# RS485_RS232_Sheet.net
KiCad netlist of a schematic drawn in Altium Designer
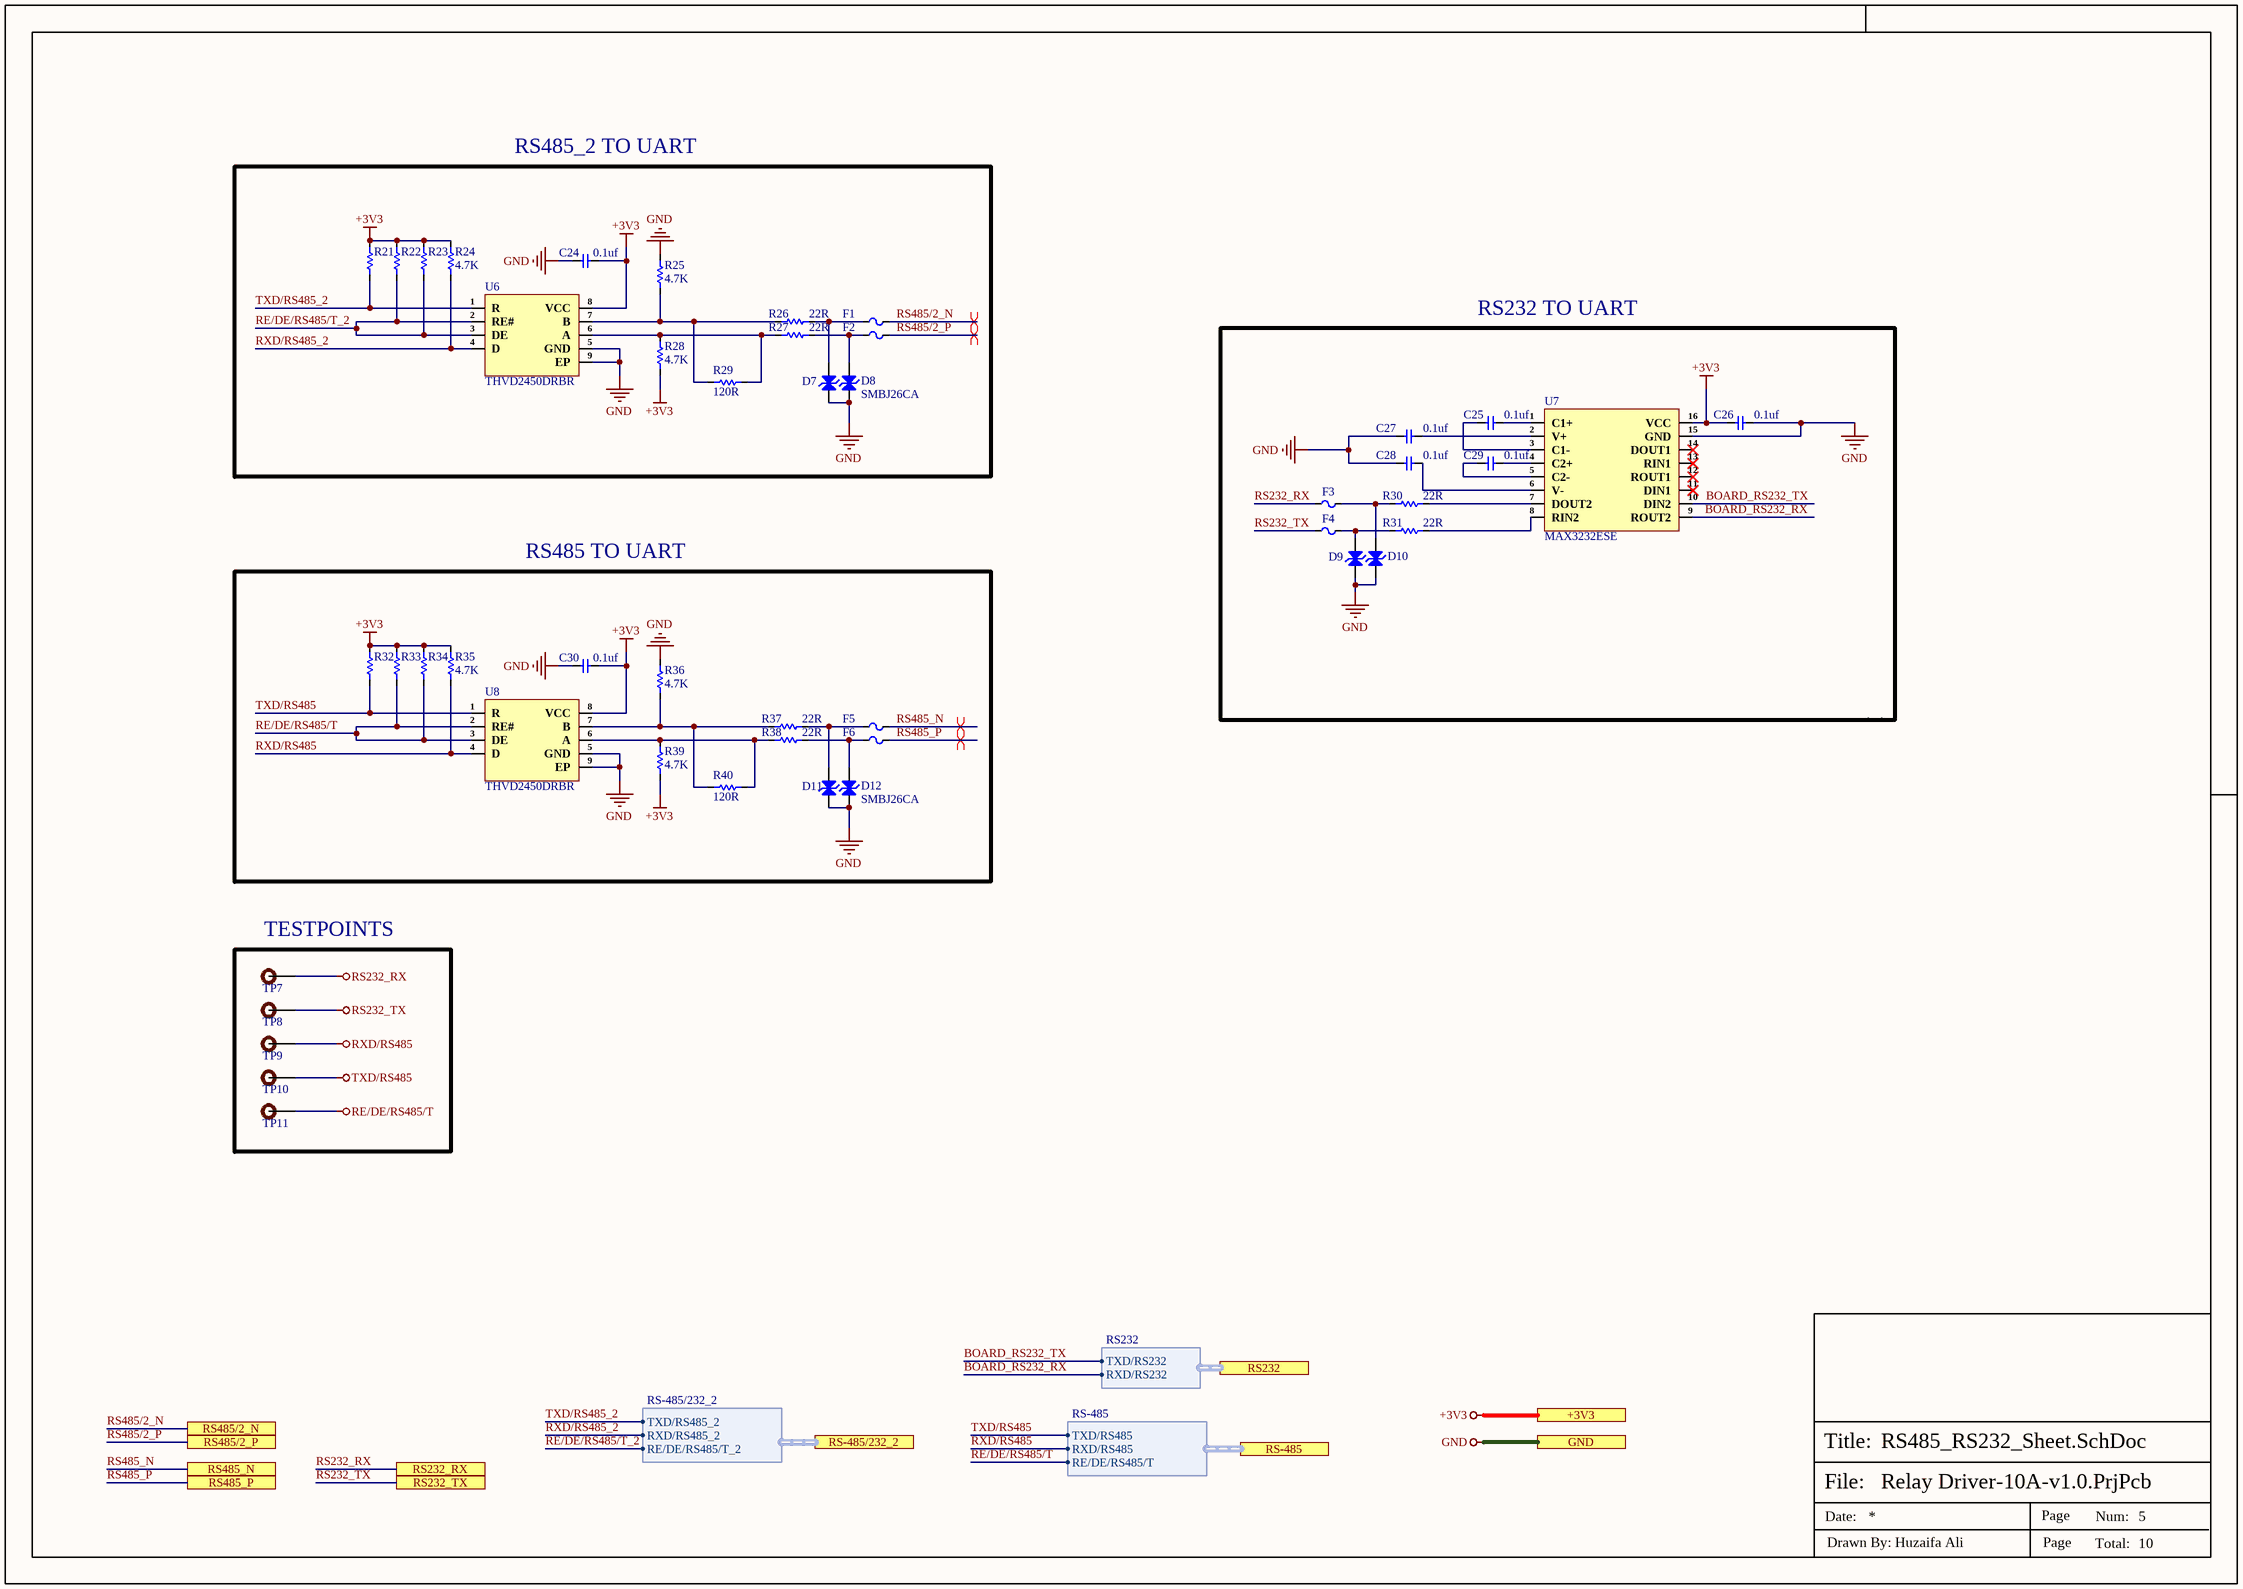
[diagram p0: RS485_RS232_Sheet.SchDoc]

(export (version "E")
  (design (tool "Eeschema 10.0.6"))
  (components
    (comp (ref "C24")
      (value "0.1uf")
      (footprint "Cap-0402")
      (description "CAP CER 0.1UF 100V X5R 0402")
      (fields
        (field (name "MANUFACTURER") "Murata")
        (field (name "MANUFACTURER PART NUMBER") "GRM155R62A104KE14D")
      )
      (libsource (lib "eSpark Libraries") (part "GRM155R62A104KE14D"))
    )
    (comp (ref "C25")
      (value "0.1uf")
      (footprint "Cap-0402")
      (description "CAP CER 0.1UF 100V X5R 0402")
      (fields
        (field (name "MANUFACTURER") "Murata")
        (field (name "MANUFACTURER PART NUMBER") "GRM155R62A104KE14D")
      )
      (libsource (lib "eSpark Libraries") (part "GRM155R62A104KE14D"))
    )
    (comp (ref "C26")
      (value "0.1uf")
      (footprint "Cap-0402")
      (description "CAP CER 0.1UF 100V X5R 0402")
      (fields
        (field (name "MANUFACTURER") "Murata")
        (field (name "MANUFACTURER PART NUMBER") "GRM155R62A104KE14D")
      )
      (libsource (lib "eSpark Libraries") (part "GRM155R62A104KE14D"))
    )
    (comp (ref "C27")
      (value "0.1uf")
      (footprint "Cap-0402")
      (description "CAP CER 0.1UF 100V X5R 0402")
      (fields
        (field (name "MANUFACTURER") "Murata")
        (field (name "MANUFACTURER PART NUMBER") "GRM155R62A104KE14D")
      )
      (libsource (lib "eSpark Libraries") (part "GRM155R62A104KE14D"))
    )
    (comp (ref "C28")
      (value "0.1uf")
      (footprint "Cap-0402")
      (description "CAP CER 0.1UF 100V X5R 0402")
      (fields
        (field (name "MANUFACTURER") "Murata")
        (field (name "MANUFACTURER PART NUMBER") "GRM155R62A104KE14D")
      )
      (libsource (lib "eSpark Libraries") (part "GRM155R62A104KE14D"))
    )
    (comp (ref "C29")
      (value "0.1uf")
      (footprint "Cap-0402")
      (description "CAP CER 0.1UF 100V X5R 0402")
      (fields
        (field (name "MANUFACTURER") "Murata")
        (field (name "MANUFACTURER PART NUMBER") "GRM155R62A104KE14D")
      )
      (libsource (lib "eSpark Libraries") (part "GRM155R62A104KE14D"))
    )
    (comp (ref "C30")
      (value "0.1uf")
      (footprint "Cap-0402")
      (description "CAP CER 0.1UF 100V X5R 0402")
      (fields
        (field (name "MANUFACTURER") "Murata")
        (field (name "MANUFACTURER PART NUMBER") "GRM155R62A104KE14D")
      )
      (libsource (lib "eSpark Libraries") (part "GRM155R62A104KE14D"))
    )
    (comp (ref "D7")
      (value "SMBJ26CA")
      (footprint "SMB Bi Directional")
      (description "SMB(DO-214AA) TVS ROHS")
      (fields (field (name "MANUFACTURER") "MSKSEMI") (field (name "LCSC PART NUMBER") "C5331111"))
      (libsource (lib "eSpark Libraries") (part "SMBJ26CA"))
    )
    (comp (ref "D8")
      (value "SMBJ26CA")
      (footprint "SMB Bi Directional")
      (description "SMB(DO-214AA) TVS ROHS")
      (fields (field (name "MANUFACTURER") "MSKSEMI") (field (name "LCSC PART NUMBER") "C5331111"))
      (libsource (lib "eSpark Libraries") (part "SMBJ26CA"))
    )
    (comp (ref "D9")
      (value "SMBJ26CA")
      (footprint "SMB Bi Directional")
      (description "SMB(DO-214AA) TVS ROHS")
      (fields (field (name "MANUFACTURER") "MSKSEMI") (field (name "LCSC PART NUMBER") "C5331111"))
      (libsource (lib "eSpark Libraries") (part "SMBJ26CA"))
    )
    (comp (ref "D10")
      (value "SMBJ26CA")
      (footprint "SMB Bi Directional")
      (description "SMB(DO-214AA) TVS ROHS")
      (fields (field (name "MANUFACTURER") "MSKSEMI") (field (name "LCSC PART NUMBER") "C5331111"))
      (libsource (lib "eSpark Libraries") (part "SMBJ26CA"))
    )
    (comp (ref "D11")
      (value "SMBJ26CA")
      (footprint "SMB Bi Directional")
      (description "SMB(DO-214AA) TVS ROHS")
      (fields (field (name "MANUFACTURER") "MSKSEMI") (field (name "LCSC PART NUMBER") "C5331111"))
      (libsource (lib "eSpark Libraries") (part "SMBJ26CA"))
    )
    (comp (ref "D12")
      (value "SMBJ26CA")
      (footprint "SMB Bi Directional")
      (description "SMB(DO-214AA) TVS ROHS")
      (fields (field (name "MANUFACTURER") "MSKSEMI") (field (name "LCSC PART NUMBER") "C5331111"))
      (libsource (lib "eSpark Libraries") (part "SMBJ26CA"))
    )
    (comp (ref "F1")
      (value "SMD0805P020TF")
      (footprint "Fuse-0805")
      (description "9V 200mA 100A 500mA 0805 Resettable Fuses ROHS")
      (fields (field (name "MANUFACTURER") "RUILON") (field (name "LCSC PART NUMBER") "C20976"))
      (libsource (lib "eSpark_centralized_Library(2022)") (part "SMD0805P020TF"))
    )
    (comp (ref "F2")
      (value "SMD0805P020TF")
      (footprint "Fuse-0805")
      (description "9V 200mA 100A 500mA 0805 Resettable Fuses ROHS")
      (fields (field (name "MANUFACTURER") "RUILON") (field (name "LCSC PART NUMBER") "C20976"))
      (libsource (lib "eSpark_centralized_Library(2022)") (part "SMD0805P020TF"))
    )
    (comp (ref "F3")
      (value "SMD0805P020TF")
      (footprint "Fuse-0805")
      (description "9V 200mA 100A 500mA 0805 Resettable Fuses ROHS")
      (fields (field (name "MANUFACTURER") "RUILON") (field (name "LCSC PART NUMBER") "C20976"))
      (libsource (lib "eSpark Libraries") (part "SMD0805P020TF"))
    )
    (comp (ref "F4")
      (value "SMD0805P020TF")
      (footprint "Fuse-0805")
      (description "9V 200mA 100A 500mA 0805 Resettable Fuses ROHS")
      (fields (field (name "MANUFACTURER") "RUILON") (field (name "LCSC PART NUMBER") "C20976"))
      (libsource (lib "eSpark Libraries") (part "SMD0805P020TF"))
    )
    (comp (ref "F5")
      (value "SMD0805P020TF")
      (footprint "Fuse-0805")
      (description "9V 200mA 100A 500mA 0805 Resettable Fuses ROHS")
      (fields (field (name "MANUFACTURER") "RUILON") (field (name "LCSC PART NUMBER") "C20976"))
      (libsource (lib "eSpark_centralized_Library(2022)") (part "SMD0805P020TF"))
    )
    (comp (ref "F6")
      (value "SMD0805P020TF")
      (footprint "Fuse-0805")
      (description "9V 200mA 100A 500mA 0805 Resettable Fuses ROHS")
      (fields (field (name "MANUFACTURER") "RUILON") (field (name "LCSC PART NUMBER") "C20976"))
      (libsource (lib "eSpark_centralized_Library(2022)") (part "SMD0805P020TF"))
    )
    (comp (ref "R21")
      (value "4.7K")
      (footprint "Res-0402")
      (description "RES 4.7K OHM 1% 1/16W 0402")
      (fields
        (field (name "MANUFACTURER") "Yageo")
        (field (name "MANUFACTURER PART NUMBER") "RC0402FR-074K7L")
      )
      (libsource (lib "eSpark Libraries") (part "RC0402FR-074K7L"))
    )
    (comp (ref "R22")
      (value "4.7K")
      (footprint "Res-0402")
      (description "RES 4.7K OHM 1% 1/16W 0402")
      (fields
        (field (name "MANUFACTURER") "Yageo")
        (field (name "MANUFACTURER PART NUMBER") "RC0402FR-074K7L")
      )
      (libsource (lib "eSpark Libraries") (part "RC0402FR-074K7L"))
    )
    (comp (ref "R23")
      (value "4.7K")
      (footprint "Res-0402")
      (description "RES 4.7K OHM 1% 1/16W 0402")
      (fields
        (field (name "MANUFACTURER") "Yageo")
        (field (name "MANUFACTURER PART NUMBER") "RC0402FR-074K7L")
      )
      (libsource (lib "eSpark Libraries") (part "RC0402FR-074K7L"))
    )
    (comp (ref "R24")
      (value "4.7K")
      (footprint "Res-0402")
      (description "RES 4.7K OHM 1% 1/16W 0402")
      (fields
        (field (name "MANUFACTURER") "Yageo")
        (field (name "MANUFACTURER PART NUMBER") "RC0402FR-074K7L")
      )
      (libsource (lib "eSpark Libraries") (part "RC0402FR-074K7L"))
    )
    (comp (ref "R25")
      (value "4.7K")
      (footprint "Res-0402")
      (description "RES 4.7K OHM 1% 1/16W 0402")
      (fields
        (field (name "MANUFACTURER") "Yageo")
        (field (name "MANUFACTURER PART NUMBER") "RC0402FR-074K7L")
      )
      (libsource (lib "eSpark Libraries") (part "RC0402FR-074K7L"))
    )
    (comp (ref "R26")
      (value "22R")
      (footprint "Res-0201")
      (description "RES 22 OHM 1% 1/20W 0201")
      (fields
        (field (name "MANUFACTURER") "Yageo")
        (field (name "MANUFACTURER PART NUMBER") "RC0201FR-0722RL")
      )
      (libsource (lib "eSpark Libraries") (part "RC0201FR-0722RL"))
    )
    (comp (ref "R27")
      (value "22R")
      (footprint "Res-0201")
      (description "RES 22 OHM 1% 1/20W 0201")
      (fields
        (field (name "MANUFACTURER") "Yageo")
        (field (name "MANUFACTURER PART NUMBER") "RC0201FR-0722RL")
      )
      (libsource (lib "eSpark Libraries") (part "RC0201FR-0722RL"))
    )
    (comp (ref "R28")
      (value "4.7K")
      (footprint "Res-0402")
      (description "RES 4.7K OHM 1% 1/16W 0402")
      (fields
        (field (name "MANUFACTURER") "Yageo")
        (field (name "MANUFACTURER PART NUMBER") "RC0402FR-074K7L")
      )
      (libsource (lib "eSpark Libraries") (part "RC0402FR-074K7L"))
    )
    (comp (ref "R29")
      (value "120R")
      (footprint "Res-0603")
      (description "RES 120 OHM 5% 1/10W 0603")
      (fields
        (field (name "MANUFACTURER") "Yageo")
        (field (name "MANUFACTURER PART NUMBER") "RC0603JR-07120RL")
      )
      (libsource (lib "eSpark Libraries") (part "RC0603JR-07120RL"))
    )
    (comp (ref "R30")
      (value "22R")
      (footprint "Res-0201")
      (description "RES 22 OHM 1% 1/20W 0201")
      (fields
        (field (name "MANUFACTURER") "Yageo")
        (field (name "MANUFACTURER PART NUMBER") "RC0201FR-0722RL")
      )
      (libsource (lib "eSpark Libraries") (part "RC0201FR-0722RL"))
    )
    (comp (ref "R31")
      (value "22R")
      (footprint "Res-0201")
      (description "RES 22 OHM 1% 1/20W 0201")
      (fields
        (field (name "MANUFACTURER") "Yageo")
        (field (name "MANUFACTURER PART NUMBER") "RC0201FR-0722RL")
      )
      (libsource (lib "eSpark Libraries") (part "RC0201FR-0722RL"))
    )
    (comp (ref "R32")
      (value "4.7K")
      (footprint "Res-0402")
      (description "RES 4.7K OHM 1% 1/16W 0402")
      (fields
        (field (name "MANUFACTURER") "Yageo")
        (field (name "MANUFACTURER PART NUMBER") "RC0402FR-074K7L")
      )
      (libsource (lib "eSpark Libraries") (part "RC0402FR-074K7L"))
    )
    (comp (ref "R33")
      (value "4.7K")
      (footprint "Res-0402")
      (description "RES 4.7K OHM 1% 1/16W 0402")
      (fields
        (field (name "MANUFACTURER") "Yageo")
        (field (name "MANUFACTURER PART NUMBER") "RC0402FR-074K7L")
      )
      (libsource (lib "eSpark Libraries") (part "RC0402FR-074K7L"))
    )
    (comp (ref "R34")
      (value "4.7K")
      (footprint "Res-0402")
      (description "RES 4.7K OHM 1% 1/16W 0402")
      (fields
        (field (name "MANUFACTURER") "Yageo")
        (field (name "MANUFACTURER PART NUMBER") "RC0402FR-074K7L")
      )
      (libsource (lib "eSpark Libraries") (part "RC0402FR-074K7L"))
    )
    (comp (ref "R35")
      (value "4.7K")
      (footprint "Res-0402")
      (description "RES 4.7K OHM 1% 1/16W 0402")
      (fields
        (field (name "MANUFACTURER") "Yageo")
        (field (name "MANUFACTURER PART NUMBER") "RC0402FR-074K7L")
      )
      (libsource (lib "eSpark Libraries") (part "RC0402FR-074K7L"))
    )
    (comp (ref "R36")
      (value "4.7K")
      (footprint "Res-0402")
      (description "RES 4.7K OHM 1% 1/16W 0402")
      (fields
        (field (name "MANUFACTURER") "Yageo")
        (field (name "MANUFACTURER PART NUMBER") "RC0402FR-074K7L")
      )
      (libsource (lib "eSpark Libraries") (part "RC0402FR-074K7L"))
    )
    (comp (ref "R37")
      (value "22R")
      (footprint "Res-0201")
      (description "RES 22 OHM 1% 1/20W 0201")
      (fields
        (field (name "MANUFACTURER") "Yageo")
        (field (name "MANUFACTURER PART NUMBER") "RC0201FR-0722RL")
      )
      (libsource (lib "eSpark Libraries") (part "RC0201FR-0722RL"))
    )
    (comp (ref "R38")
      (value "22R")
      (footprint "Res-0201")
      (description "RES 22 OHM 1% 1/20W 0201")
      (fields
        (field (name "MANUFACTURER") "Yageo")
        (field (name "MANUFACTURER PART NUMBER") "RC0201FR-0722RL")
      )
      (libsource (lib "eSpark Libraries") (part "RC0201FR-0722RL"))
    )
    (comp (ref "R39")
      (value "4.7K")
      (footprint "Res-0402")
      (description "RES 4.7K OHM 1% 1/16W 0402")
      (fields
        (field (name "MANUFACTURER") "Yageo")
        (field (name "MANUFACTURER PART NUMBER") "RC0402FR-074K7L")
      )
      (libsource (lib "eSpark Libraries") (part "RC0402FR-074K7L"))
    )
    (comp (ref "R40")
      (value "120R")
      (footprint "Res-0603")
      (description "RES 120 OHM 5% 1/10W 0603")
      (fields
        (field (name "MANUFACTURER") "Yageo")
        (field (name "MANUFACTURER PART NUMBER") "RC0603JR-07120RL")
      )
      (libsource (lib "eSpark Libraries") (part "RC0603JR-07120RL"))
    )
    (comp (ref "TP7")
      (value "TEST POINT")
      (footprint "Test-point")
      (description "Test Point ON")
      (libsource (lib "eSpark Libraries") (part "TEST POINT"))
    )
    (comp (ref "TP8")
      (value "TEST POINT")
      (footprint "Test-point")
      (description "Test Point ON")
      (libsource (lib "eSpark Libraries") (part "TEST POINT"))
    )
    (comp (ref "TP9")
      (value "TEST POINT")
      (footprint "Test-point")
      (description "Test Point ON")
      (libsource (lib "eSpark Libraries") (part "TEST POINT"))
    )
    (comp (ref "TP10")
      (value "TEST POINT")
      (footprint "Test-point")
      (description "Test Point ON")
      (libsource (lib "eSpark Libraries") (part "TEST POINT"))
    )
    (comp (ref "TP11")
      (value "TEST POINT")
      (footprint "Test-point")
      (description "Test Point ON")
      (libsource (lib "eSpark Libraries") (part "TEST POINT"))
    )
    (comp (ref "U6")
      (value "THVD2450DRBR")
      (footprint "SON-8-EP(3x3)")
      (description "IC TRANSCEIVER HALF 1/1 8SON")
      (fields (field (name "MANUFACTURER") "Texas Instruments") (field (name "LCSC PART NUMBER") "C2878080"))
      (libsource (lib "eSpark Libraries") (part "THVD2450DRBR"))
    )
    (comp (ref "U7")
      (value "MAX3232ESE")
      (footprint "SOP-16")
      (description "250Kbps transceiver 2/2 SOP-16 RS232 ICs ROHS")
      (fields (field (name "MANUFACTURER") "UMW") (field (name "LCSC PART NUMBER") "C2904738"))
      (libsource (lib "eSpark Libraries") (part "MAX3232ESE"))
    )
    (comp (ref "U8")
      (value "THVD2450DRBR")
      (footprint "SON-8-EP(3x3)")
      (description "IC TRANSCEIVER HALF 1/1 8SON")
      (fields (field (name "MANUFACTURER") "Texas Instruments") (field (name "LCSC PART NUMBER") "C2878080"))
      (libsource (lib "eSpark Libraries") (part "THVD2450DRBR"))
    )
  )
  (nets
    (net (code "4") (name "+3V3") (class "Default")
      (node (ref "C24") (pin "2") (pinfunction "2_2") (pintype "passive"))
      (node (ref "C26") (pin "2") (pinfunction "2_2") (pintype "passive"))
      (node (ref "C30") (pin "2") (pinfunction "2_2") (pintype "passive"))
      (node (ref "R21") (pin "2") (pinfunction "2_2") (pintype "passive"))
      (node (ref "R22") (pin "2") (pinfunction "2_2") (pintype "passive"))
      (node (ref "R23") (pin "2") (pinfunction "2_2") (pintype "passive"))
      (node (ref "R24") (pin "2") (pinfunction "2_2") (pintype "passive"))
      (node (ref "R28") (pin "1") (pinfunction "1_1") (pintype "passive"))
      (node (ref "R32") (pin "2") (pinfunction "2_2") (pintype "passive"))
      (node (ref "R33") (pin "2") (pinfunction "2_2") (pintype "passive"))
      (node (ref "R34") (pin "2") (pinfunction "2_2") (pintype "passive"))
      (node (ref "R35") (pin "2") (pinfunction "2_2") (pintype "passive"))
      (node (ref "R39") (pin "1") (pinfunction "1_1") (pintype "passive"))
      (node (ref "U6") (pin "8") (pinfunction "VCC_8") (pintype "passive"))
      (node (ref "U7") (pin "16") (pinfunction "VCC_16") (pintype "passive"))
      (node (ref "U8") (pin "8") (pinfunction "VCC_8") (pintype "passive"))
    )
    (net (code "5") (name "/BOARD_RS232_RX") (class "Default")
      (node (ref "U7") (pin "9") (pinfunction "ROUT2_9") (pintype "passive"))
    )
    (net (code "6") (name "/BOARD_RS232_TX") (class "Default")
      (node (ref "U7") (pin "10") (pinfunction "DIN2_10") (pintype "passive"))
    )
    (net (code "7") (name "/RE{slash}DE{slash}RS485{slash}T_2") (class "Default")
      (node (ref "R22") (pin "1") (pinfunction "1_1") (pintype "passive"))
      (node (ref "R23") (pin "1") (pinfunction "1_1") (pintype "passive"))
      (node (ref "U6") (pin "2") (pinfunction "RE#_2") (pintype "passive"))
      (node (ref "U6") (pin "3") (pinfunction "DE_3") (pintype "passive"))
    )
    (net (code "8") (name "/RS485_N") (class "Default")
      (node (ref "F5") (pin "2") (pinfunction "2_2") (pintype "passive"))
    )
    (net (code "9") (name "/RS485_P") (class "Default")
      (node (ref "F6") (pin "2") (pinfunction "2_2") (pintype "passive"))
    )
    (net (code "10") (name "/RS485{slash}2_N") (class "Default")
      (node (ref "F1") (pin "2") (pinfunction "2_2") (pintype "passive"))
    )
    (net (code "11") (name "/RS485{slash}2_P") (class "Default")
      (node (ref "F2") (pin "2") (pinfunction "2_2") (pintype "passive"))
    )
    (net (code "12") (name "/RXD{slash}RS485_2") (class "Default")
      (node (ref "R24") (pin "1") (pinfunction "1_1") (pintype "passive"))
      (node (ref "U6") (pin "4") (pinfunction "D_4") (pintype "passive"))
    )
    (net (code "13") (name "/TXD{slash}RS485_2") (class "Default")
      (node (ref "R21") (pin "1") (pinfunction "1_1") (pintype "passive"))
      (node (ref "U6") (pin "1") (pinfunction "R_1") (pintype "passive"))
    )
    (net (code "17") (name "GND") (class "Default")
      (node (ref "C24") (pin "1") (pinfunction "1_1") (pintype "passive"))
      (node (ref "C26") (pin "1") (pinfunction "1_1") (pintype "passive"))
      (node (ref "C27") (pin "1") (pinfunction "1_1") (pintype "passive"))
      (node (ref "C28") (pin "1") (pinfunction "1_1") (pintype "passive"))
      (node (ref "C30") (pin "1") (pinfunction "1_1") (pintype "passive"))
      (node (ref "D10") (pin "1") (pinfunction "A_1") (pintype "passive"))
      (node (ref "D11") (pin "1") (pinfunction "A_1") (pintype "passive"))
      (node (ref "D12") (pin "1") (pinfunction "A_1") (pintype "passive"))
      (node (ref "D7") (pin "1") (pinfunction "A_1") (pintype "passive"))
      (node (ref "D8") (pin "1") (pinfunction "A_1") (pintype "passive"))
      (node (ref "D9") (pin "1") (pinfunction "A_1") (pintype "passive"))
      (node (ref "R25") (pin "2") (pinfunction "2_2") (pintype "passive"))
      (node (ref "R36") (pin "2") (pinfunction "2_2") (pintype "passive"))
      (node (ref "U6") (pin "5") (pinfunction "GND_5") (pintype "passive"))
      (node (ref "U6") (pin "9") (pinfunction "EP_9") (pintype "passive"))
      (node (ref "U7") (pin "15") (pinfunction "GND_15") (pintype "passive"))
      (node (ref "U8") (pin "5") (pinfunction "GND_5") (pintype "passive"))
      (node (ref "U8") (pin "9") (pinfunction "EP_9") (pintype "passive"))
    )
    (net (code "18") (name "Net-(D7-K)") (class "Default")
      (node (ref "D7") (pin "2") (pinfunction "K_2") (pintype "passive"))
      (node (ref "F1") (pin "1") (pinfunction "1_1") (pintype "passive"))
      (node (ref "R26") (pin "2") (pinfunction "2_2") (pintype "passive"))
    )
    (net (code "19") (name "Net-(D8-K)") (class "Default")
      (node (ref "D8") (pin "2") (pinfunction "K_2") (pintype "passive"))
      (node (ref "F2") (pin "1") (pinfunction "1_1") (pintype "passive"))
      (node (ref "R27") (pin "2") (pinfunction "2_2") (pintype "passive"))
    )
    (net (code "20") (name "Net-(D9-K)") (class "Default")
      (node (ref "D9") (pin "2") (pinfunction "K_2") (pintype "passive"))
      (node (ref "F4") (pin "2") (pinfunction "2_2") (pintype "passive"))
      (node (ref "R31") (pin "1") (pinfunction "1_1") (pintype "passive"))
    )
    (net (code "21") (name "Net-(D10-K)") (class "Default")
      (node (ref "D10") (pin "2") (pinfunction "K_2") (pintype "passive"))
      (node (ref "F3") (pin "2") (pinfunction "2_2") (pintype "passive"))
      (node (ref "R30") (pin "1") (pinfunction "1_1") (pintype "passive"))
    )
    (net (code "22") (name "Net-(D11-K)") (class "Default")
      (node (ref "D11") (pin "2") (pinfunction "K_2") (pintype "passive"))
      (node (ref "F5") (pin "1") (pinfunction "1_1") (pintype "passive"))
      (node (ref "R37") (pin "2") (pinfunction "2_2") (pintype "passive"))
    )
    (net (code "23") (name "Net-(D12-K)") (class "Default")
      (node (ref "D12") (pin "2") (pinfunction "K_2") (pintype "passive"))
      (node (ref "F6") (pin "1") (pinfunction "1_1") (pintype "passive"))
      (node (ref "R38") (pin "2") (pinfunction "2_2") (pintype "passive"))
    )
    (net (code "24") (name "Net-(U6-A)") (class "Default")
      (node (ref "R27") (pin "1") (pinfunction "1_1") (pintype "passive"))
      (node (ref "R28") (pin "2") (pinfunction "2_2") (pintype "passive"))
      (node (ref "R29") (pin "2") (pinfunction "2_2") (pintype "passive"))
      (node (ref "U6") (pin "6") (pinfunction "A_6") (pintype "passive"))
    )
    (net (code "25") (name "Net-(U6-B)") (class "Default")
      (node (ref "R25") (pin "1") (pinfunction "1_1") (pintype "passive"))
      (node (ref "R26") (pin "1") (pinfunction "1_1") (pintype "passive"))
      (node (ref "R29") (pin "1") (pinfunction "1_1") (pintype "passive"))
      (node (ref "U6") (pin "7") (pinfunction "B_7") (pintype "passive"))
    )
    (net (code "26") (name "Net-(U7-C1+)") (class "Default")
      (node (ref "C25") (pin "1") (pinfunction "1_1") (pintype "passive"))
      (node (ref "U7") (pin "1") (pinfunction "C1+_1") (pintype "passive"))
    )
    (net (code "27") (name "Net-(U7-C1-)") (class "Default")
      (node (ref "C25") (pin "2") (pinfunction "2_2") (pintype "passive"))
      (node (ref "U7") (pin "3") (pinfunction "C1-_3") (pintype "passive"))
    )
    (net (code "28") (name "Net-(U7-C2+)") (class "Default")
      (node (ref "C29") (pin "1") (pinfunction "1_1") (pintype "passive"))
      (node (ref "U7") (pin "4") (pinfunction "C2+_4") (pintype "passive"))
    )
    (net (code "29") (name "Net-(U7-C2-)") (class "Default")
      (node (ref "C29") (pin "2") (pinfunction "2_2") (pintype "passive"))
      (node (ref "U7") (pin "5") (pinfunction "C2-_5") (pintype "passive"))
    )
    (net (code "30") (name "Net-(U7-DOUT2)") (class "Default")
      (node (ref "R30") (pin "2") (pinfunction "2_2") (pintype "passive"))
      (node (ref "U7") (pin "7") (pinfunction "DOUT2_7") (pintype "passive"))
    )
    (net (code "31") (name "Net-(U7-RIN2)") (class "Default")
      (node (ref "R31") (pin "2") (pinfunction "2_2") (pintype "passive"))
      (node (ref "U7") (pin "8") (pinfunction "RIN2_8") (pintype "passive"))
    )
    (net (code "32") (name "Net-(U7-V+)") (class "Default")
      (node (ref "C27") (pin "2") (pinfunction "2_2") (pintype "passive"))
      (node (ref "U7") (pin "2") (pinfunction "V+_2") (pintype "passive"))
    )
    (net (code "33") (name "Net-(U7-V-)") (class "Default")
      (node (ref "C28") (pin "2") (pinfunction "2_2") (pintype "passive"))
      (node (ref "U7") (pin "6") (pinfunction "V-_6") (pintype "passive"))
    )
    (net (code "34") (name "Net-(U8-A)") (class "Default")
      (node (ref "R38") (pin "1") (pinfunction "1_1") (pintype "passive"))
      (node (ref "R39") (pin "2") (pinfunction "2_2") (pintype "passive"))
      (node (ref "R40") (pin "2") (pinfunction "2_2") (pintype "passive"))
      (node (ref "U8") (pin "6") (pinfunction "A_6") (pintype "passive"))
    )
    (net (code "35") (name "Net-(U8-B)") (class "Default")
      (node (ref "R36") (pin "1") (pinfunction "1_1") (pintype "passive"))
      (node (ref "R37") (pin "1") (pinfunction "1_1") (pintype "passive"))
      (node (ref "R40") (pin "1") (pinfunction "1_1") (pintype "passive"))
      (node (ref "U8") (pin "7") (pinfunction "B_7") (pintype "passive"))
    )
    (net (code "36") (name "RE{slash}DE{slash}RS485{slash}T") (class "Default")
      (node (ref "R33") (pin "1") (pinfunction "1_1") (pintype "passive"))
      (node (ref "R34") (pin "1") (pinfunction "1_1") (pintype "passive"))
      (node (ref "TP11") (pin "1") (pinfunction "1_1") (pintype "passive"))
      (node (ref "U8") (pin "2") (pinfunction "RE#_2") (pintype "passive"))
      (node (ref "U8") (pin "3") (pinfunction "DE_3") (pintype "passive"))
    )
    (net (code "37") (name "RS232_RX") (class "Default")
      (node (ref "F3") (pin "1") (pinfunction "1_1") (pintype "passive"))
      (node (ref "TP7") (pin "1") (pinfunction "1_1") (pintype "passive"))
    )
    (net (code "38") (name "RS232_TX") (class "Default")
      (node (ref "F4") (pin "1") (pinfunction "1_1") (pintype "passive"))
      (node (ref "TP8") (pin "1") (pinfunction "1_1") (pintype "passive"))
    )
    (net (code "39") (name "RXD{slash}RS485") (class "Default")
      (node (ref "R35") (pin "1") (pinfunction "1_1") (pintype "passive"))
      (node (ref "TP9") (pin "1") (pinfunction "1_1") (pintype "passive"))
      (node (ref "U8") (pin "4") (pinfunction "D_4") (pintype "passive"))
    )
    (net (code "40") (name "TXD{slash}RS485") (class "Default")
      (node (ref "R32") (pin "1") (pinfunction "1_1") (pintype "passive"))
      (node (ref "TP10") (pin "1") (pinfunction "1_1") (pintype "passive"))
      (node (ref "U8") (pin "1") (pinfunction "R_1") (pintype "passive"))
    )
    (net (code "41") (name "unconnected-(U7-DIN1-Pad11)") (class "Default")
      (node (ref "U7") (pin "11") (pinfunction "DIN1_11") (pintype "passive+no_connect"))
    )
    (net (code "42") (name "unconnected-(U7-DOUT1-Pad14)") (class "Default")
      (node (ref "U7") (pin "14") (pinfunction "DOUT1_14") (pintype "passive+no_connect"))
    )
    (net (code "43") (name "unconnected-(U7-RIN1-Pad13)") (class "Default")
      (node (ref "U7") (pin "13") (pinfunction "RIN1_13") (pintype "passive+no_connect"))
    )
    (net (code "44") (name "unconnected-(U7-ROUT1-Pad12)") (class "Default")
      (node (ref "U7") (pin "12") (pinfunction "ROUT1_12") (pintype "passive+no_connect"))
    )
  )
)
